# Battery_Charger.net
KiCad netlist of a schematic drawn in Altium Designer
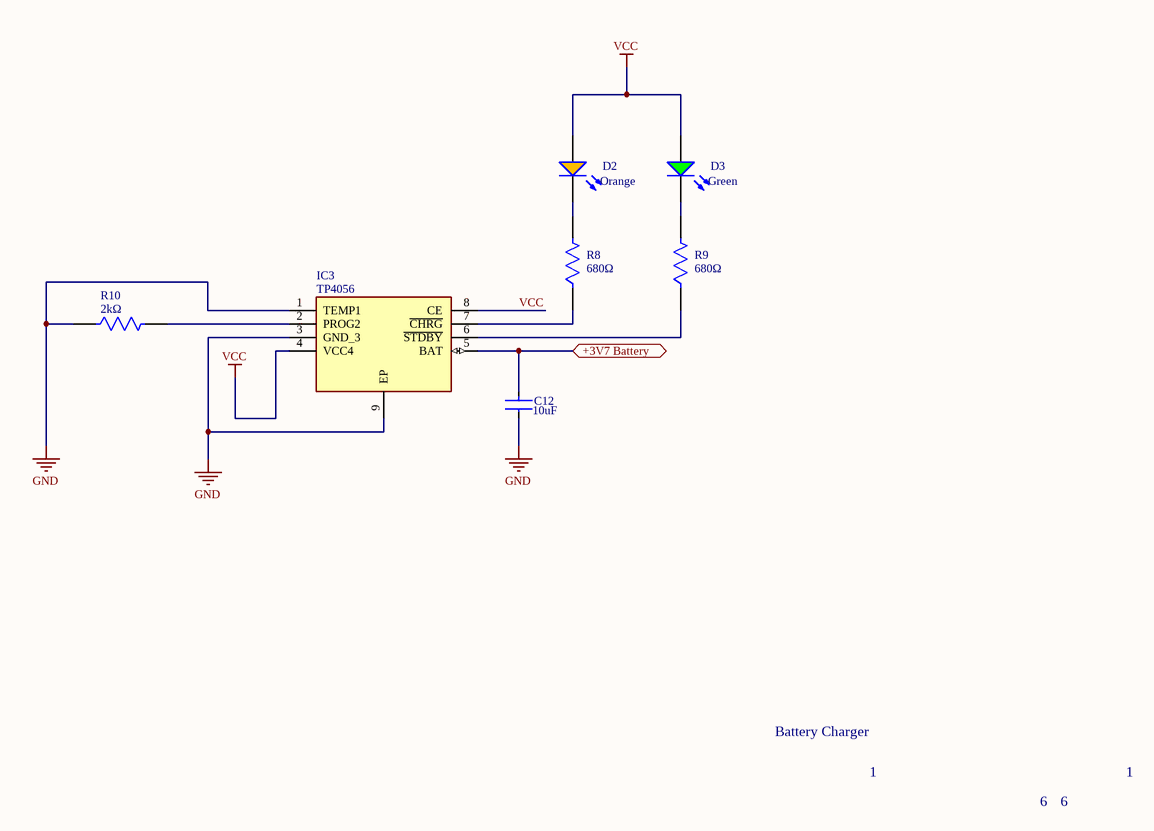
[diagram p0: Battery Charger.SchDoc]

(export (version "E")
  (design (tool "Eeschema 10.0.6"))
  (components
    (comp (ref "C12")
      (value "10uF")
      (footprint "FP-GCM21B-0_2-e0_2_0_7-MFG")
      (description "10 µF ±10% 25V Ceramic Capacitor X7S 0805 (2012 Metric)")
      (fields (field (name "Comment") "GCM21BC71E106KE36L"))
      (libsource (lib "Altium Content Vault") (part "11868f565c42a9108669ba33697ecf6"))
    )
    (comp (ref "D2")
      (value "150120AS75000")
      (footprint "WL-SMCW_1206_150120xx75000")
      (fields (field (name "COLOR") "Orange"))
      (libsource (lib "Altium Content Vault") (part "LED_Amber_2A-1K"))
    )
    (comp (ref "D3")
      (value "150120GS75000")
      (footprint "WL-SMCW_1206_150120xx75000")
      (fields (field (name "COLOR") "Green"))
      (libsource (lib "Altium Content Vault") (part "LED_Green_2A-1K"))
    )
    (comp (ref "IC3")
      (value "TP4056")
      (footprint "SamacSys:SOIC127P600X175-9N")
      (description "Connector")
      (libsource (lib "*") (part "TP4056"))
    )
    (comp (ref "R8")
      (value "680Ω")
      (footprint "FP-MCU0805-MFG")
      (description "RES 1.05K OHM 0.5% 1/5W 0805")
      (fields (field (name "TOLERANCE") "0.1%") (field (name "Comment") "MCU08050D6800BP500"))
      (libsource (lib "Altium Content Vault") (part "1029c3af85768c4190bb7ad29bc67b5"))
    )
    (comp (ref "R9")
      (value "680Ω")
      (footprint "FP-MCU0805-MFG")
      (description "RES 1.05K OHM 0.5% 1/5W 0805")
      (fields (field (name "TOLERANCE") "0.1%") (field (name "Comment") "MCU08050D6800BP500"))
      (libsource (lib "Altium Content Vault") (part "1029c3af85768c4190bb7ad29bc67b5"))
    )
    (comp (ref "R10")
      (value "2kΩ")
      (footprint "FP-RC2012-MFG")
      (description "Res Thick Film 0805 2kΩ 1% 0.125W ±100ppm/°C Molded SMD T/R")
      (fields (field (name "TOLERANCE") "1%") (field (name "Comment") "RC2012F202CS"))
      (libsource (lib "Altium Content Vault") (part "1029c3af85768c4190bb7ad29bc67b5"))
    )
  )
  (nets
    (net (code "1") (name "/+3V7 Battery") (class "Default")
      (node (ref "C12") (pin "1") (pinfunction "1_1") (pintype "passive"))
      (node (ref "IC3") (pin "5") (pinfunction "BAT_5") (pintype "bidirectional"))
    )
    (net (code "2") (name "GND") (class "Default")
      (node (ref "C12") (pin "2") (pinfunction "2_2") (pintype "passive"))
      (node (ref "IC3") (pin "1") (pinfunction "TEMP1_1") (pintype "passive"))
      (node (ref "IC3") (pin "3") (pinfunction "GND_3_3") (pintype "passive"))
      (node (ref "IC3") (pin "9") (pinfunction "EP_9") (pintype "passive"))
      (node (ref "R10") (pin "1") (pinfunction "1_1") (pintype "passive"))
    )
    (net (code "3") (name "Net-(D2-K)") (class "Default")
      (node (ref "D2") (pin "1") (pinfunction "K_1") (pintype "passive"))
      (node (ref "R8") (pin "2") (pinfunction "2_2") (pintype "passive"))
    )
    (net (code "4") (name "Net-(D3-K)") (class "Default")
      (node (ref "D3") (pin "1") (pinfunction "K_1") (pintype "passive"))
      (node (ref "R9") (pin "2") (pinfunction "2_2") (pintype "passive"))
    )
    (net (code "5") (name "Net-(IC3-PROG2)") (class "Default")
      (node (ref "IC3") (pin "2") (pinfunction "PROG2_2") (pintype "passive"))
      (node (ref "R10") (pin "2") (pinfunction "2_2") (pintype "passive"))
    )
    (net (code "6") (name "Net-(IC3-~{CHRG})") (class "Default")
      (node (ref "IC3") (pin "7") (pinfunction "~{CHRG}_7") (pintype "passive"))
      (node (ref "R8") (pin "1") (pinfunction "1_1") (pintype "passive"))
    )
    (net (code "7") (name "Net-(IC3-~{STDBY})") (class "Default")
      (node (ref "IC3") (pin "6") (pinfunction "~{STDBY}_6") (pintype "passive"))
      (node (ref "R9") (pin "1") (pinfunction "1_1") (pintype "passive"))
    )
    (net (code "8") (name "VCC") (class "Default")
      (node (ref "D2") (pin "2") (pinfunction "A_2") (pintype "passive"))
      (node (ref "D3") (pin "2") (pinfunction "A_2") (pintype "passive"))
      (node (ref "IC3") (pin "4") (pinfunction "VCC4_4") (pintype "passive"))
      (node (ref "IC3") (pin "8") (pinfunction "CE_8") (pintype "passive"))
    )
  )
)
